# Interface.net
KiCad netlist of a schematic drawn in Altium Designer
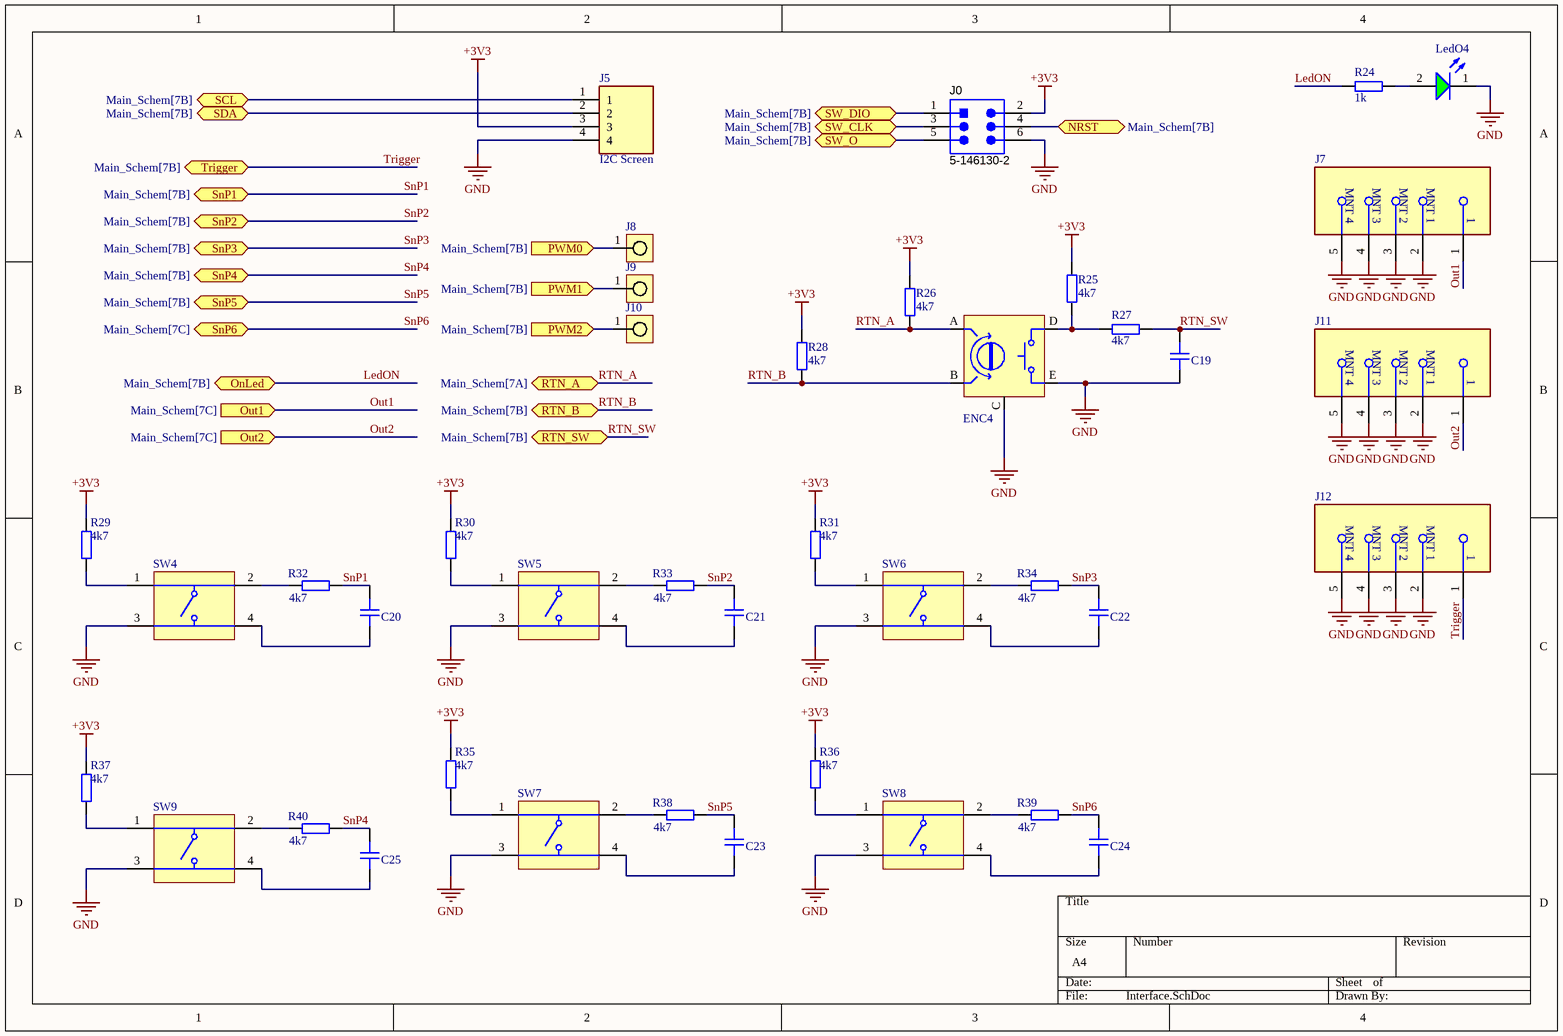
[diagram p0: Interface.SchDoc]

(export (version "E")
  (design (tool "Eeschema 10.0.6"))
  (components
    (comp (ref "C19")
      (value "CAP_0805")
      (footprint "CAP_0805")
      (description "Capacitor SMD 0805")
      (fields (field (name "SOURCE") "Kostas_Psarras_Schem_Lib.SchLib"))
      (libsource (lib "Konstantinos Psarras") (part "CAP_EL_NP_5MM"))
    )
    (comp (ref "C20")
      (value "CAP_0805")
      (footprint "CAP_0805")
      (description "Capacitor SMD 0805")
      (fields (field (name "SOURCE") "Kostas_Psarras_Schem_Lib.SchLib"))
      (libsource (lib "Konstantinos Psarras") (part "CAP_EL_NP_5MM"))
    )
    (comp (ref "C21")
      (value "CAP_0805")
      (footprint "CAP_0805")
      (description "Capacitor SMD 0805")
      (fields (field (name "SOURCE") "Kostas_Psarras_Schem_Lib.SchLib"))
      (libsource (lib "Konstantinos Psarras") (part "CAP_EL_NP_5MM"))
    )
    (comp (ref "C22")
      (value "CAP_0805")
      (footprint "CAP_0805")
      (description "Capacitor SMD 0805")
      (fields (field (name "SOURCE") "Kostas_Psarras_Schem_Lib.SchLib"))
      (libsource (lib "Konstantinos Psarras") (part "CAP_EL_NP_5MM"))
    )
    (comp (ref "C23")
      (value "CAP_0805")
      (footprint "CAP_0805")
      (description "Capacitor SMD 0805")
      (fields (field (name "SOURCE") "Kostas_Psarras_Schem_Lib.SchLib"))
      (libsource (lib "Konstantinos Psarras") (part "CAP_EL_NP_5MM"))
    )
    (comp (ref "C24")
      (value "CAP_0805")
      (footprint "CAP_0805")
      (description "Capacitor SMD 0805")
      (fields (field (name "SOURCE") "Kostas_Psarras_Schem_Lib.SchLib"))
      (libsource (lib "Konstantinos Psarras") (part "CAP_EL_NP_5MM"))
    )
    (comp (ref "C25")
      (value "CAP_0805")
      (footprint "CAP_0805")
      (description "Capacitor SMD 0805")
      (fields (field (name "SOURCE") "Kostas_Psarras_Schem_Lib.SchLib"))
      (libsource (lib "Konstantinos Psarras") (part "CAP_EL_NP_5MM"))
    )
    (comp (ref "ENC4")
      (value "EN11-HSM1BF20")
      (footprint "EN11-HSM")
      (description "Rotary Encoder with Switch 20 Detents 7mm Bushing 20mm Threaded Shaft Vertical")
      (fields (field (name "MANUFACTURER") "TT Electronics"))
      (libsource (lib "Kostas_Psarras_Lib") (part "EN11-HSM1BF20"))
    )
    (comp (ref "J0")
      (value "5-146130-2")
      (footprint "TECO-5-146130-2_V")
      (description "Male Header, Pitch 2.54 mm, 2 x 3 Position, Height 8.13 mm, -65 to 125 degC, RoHS, Tube")
      (fields (field (name "MANUFACTURER") "TE Connectivity"))
      (libsource (lib "Konstantinos Psarras") (part "CN-2P-M-R6"))
    )
    (comp (ref "J5")
      (value "I2C Screen")
      (footprint "RHDR4W70P0X254_1X4_1056X250X850P")
      (description "M20: 4 Pos Receptacle SIL Straight 3mm THT Connector 8.5mm high Tin")
      (fields
        (field (name "MANUFACTURER_PART_NUMBER") "M20-7820446")
        (field (name "MOUSER PART NUMBER") "855-M20-7820446")
        (field (name "SOURCE") "Kostas_Psarras_Schem_Lib.SchLib")
      )
      (libsource (lib "Konstantinos Psarras") (part "M20-7820446"))
    )
    (comp (ref "J7")
      (value "1-1337445-0")
      (footprint "FP-1-1337445-0-MFG")
      (description "CONN BNC JACK STR 50 OHM PCB")
      (libsource (lib "Altium Content Vault") (part "c65b8a639cdaef1819ea20b5466f8fa"))
    )
    (comp (ref "J8")
      (value "SOLDER_PIN_THT")
      (footprint "SOLDER_PIN_THT_1_5")
      (description "Solder Pin 1.5mm Through-Hole")
      (fields (field (name "SOURCE") "Kostas_Psarras_Schem_Lib.SchLib"))
      (libsource (lib "Konstantinos Psarras") (part "SOLDER_PIN_THT"))
    )
    (comp (ref "J9")
      (value "SOLDER_PIN_THT")
      (footprint "SOLDER_PIN_THT_1_5")
      (description "Solder Pin 1.5mm Through-Hole")
      (fields (field (name "SOURCE") "Kostas_Psarras_Schem_Lib.SchLib"))
      (libsource (lib "Konstantinos Psarras") (part "SOLDER_PIN_THT"))
    )
    (comp (ref "J10")
      (value "SOLDER_PIN_THT")
      (footprint "SOLDER_PIN_THT_1_5")
      (description "Solder Pin 1.5mm Through-Hole")
      (fields (field (name "SOURCE") "Kostas_Psarras_Schem_Lib.SchLib"))
      (libsource (lib "Konstantinos Psarras") (part "SOLDER_PIN_THT"))
    )
    (comp (ref "J11")
      (value "1-1337445-0")
      (footprint "FP-1-1337445-0-MFG")
      (description "CONN BNC JACK STR 50 OHM PCB")
      (libsource (lib "Altium Content Vault") (part "c65b8a639cdaef1819ea20b5466f8fa"))
    )
    (comp (ref "J12")
      (value "1-1337445-0")
      (footprint "FP-1-1337445-0-MFG")
      (description "CONN BNC JACK STR 50 OHM PCB")
      (libsource (lib "Altium Content Vault") (part "c65b8a639cdaef1819ea20b5466f8fa"))
    )
    (comp (ref "LedO4")
      (value "151053GS03000")
      (footprint "WL-TMRW_D5.8H11.7")
      (libsource (lib "Altium Content Vault") (part "LED_Green_2A-1K"))
    )
    (comp (ref "R24")
      (value "1k")
      (footprint "RES_0805")
      (description "Resistor SMD 0805")
      (libsource (lib "Schematic-Lib-PhilsLab (1)") (part "RES_0805"))
    )
    (comp (ref "R25")
      (value "4k7")
      (footprint "RES_0805")
      (description "Resistor SMD 0805")
      (fields (field (name "SOURCE") "Kostas_Psarras_Schem_Lib.SchLib"))
      (libsource (lib "Konstantinos Psarras") (part "RES_5931"))
    )
    (comp (ref "R26")
      (value "4k7")
      (footprint "RES_0805")
      (description "Resistor SMD 0805")
      (fields (field (name "SOURCE") "Kostas_Psarras_Schem_Lib.SchLib"))
      (libsource (lib "Konstantinos Psarras") (part "RES_5931"))
    )
    (comp (ref "R27")
      (value "4k7")
      (footprint "RES_0805")
      (description "Resistor SMD 0805")
      (fields (field (name "SOURCE") "Kostas_Psarras_Schem_Lib.SchLib"))
      (libsource (lib "Konstantinos Psarras") (part "RES_5931"))
    )
    (comp (ref "R28")
      (value "4k7")
      (footprint "RES_0805")
      (description "Resistor SMD 0805")
      (fields (field (name "SOURCE") "Kostas_Psarras_Schem_Lib.SchLib"))
      (libsource (lib "Konstantinos Psarras") (part "RES_5931"))
    )
    (comp (ref "R29")
      (value "4k7")
      (footprint "RES_0805")
      (description "Resistor SMD 0805")
      (fields (field (name "SOURCE") "Kostas_Psarras_Schem_Lib.SchLib"))
      (libsource (lib "Konstantinos Psarras") (part "RES_5931"))
    )
    (comp (ref "R30")
      (value "4k7")
      (footprint "RES_0805")
      (description "Resistor SMD 0805")
      (fields (field (name "SOURCE") "Kostas_Psarras_Schem_Lib.SchLib"))
      (libsource (lib "Konstantinos Psarras") (part "RES_5931"))
    )
    (comp (ref "R31")
      (value "4k7")
      (footprint "RES_0805")
      (description "Resistor SMD 0805")
      (fields (field (name "SOURCE") "Kostas_Psarras_Schem_Lib.SchLib"))
      (libsource (lib "Konstantinos Psarras") (part "RES_5931"))
    )
    (comp (ref "R32")
      (value "4k7")
      (footprint "RES_0805")
      (description "Resistor SMD 0805")
      (fields (field (name "SOURCE") "Kostas_Psarras_Schem_Lib.SchLib"))
      (libsource (lib "Konstantinos Psarras") (part "RES_5931"))
    )
    (comp (ref "R33")
      (value "4k7")
      (footprint "RES_0805")
      (description "Resistor SMD 0805")
      (fields (field (name "SOURCE") "Kostas_Psarras_Schem_Lib.SchLib"))
      (libsource (lib "Konstantinos Psarras") (part "RES_5931"))
    )
    (comp (ref "R34")
      (value "4k7")
      (footprint "RES_0805")
      (description "Resistor SMD 0805")
      (fields (field (name "SOURCE") "Kostas_Psarras_Schem_Lib.SchLib"))
      (libsource (lib "Konstantinos Psarras") (part "RES_5931"))
    )
    (comp (ref "R35")
      (value "4k7")
      (footprint "RES_0805")
      (description "Resistor SMD 0805")
      (fields (field (name "SOURCE") "Kostas_Psarras_Schem_Lib.SchLib"))
      (libsource (lib "Konstantinos Psarras") (part "RES_5931"))
    )
    (comp (ref "R36")
      (value "4k7")
      (footprint "RES_0805")
      (description "Resistor SMD 0805")
      (fields (field (name "SOURCE") "Kostas_Psarras_Schem_Lib.SchLib"))
      (libsource (lib "Konstantinos Psarras") (part "RES_5931"))
    )
    (comp (ref "R37")
      (value "4k7")
      (footprint "RES_0805")
      (description "Resistor SMD 0805")
      (fields (field (name "SOURCE") "Kostas_Psarras_Schem_Lib.SchLib"))
      (libsource (lib "Konstantinos Psarras") (part "RES_5931"))
    )
    (comp (ref "R38")
      (value "4k7")
      (footprint "RES_0805")
      (description "Resistor SMD 0805")
      (fields (field (name "SOURCE") "Kostas_Psarras_Schem_Lib.SchLib"))
      (libsource (lib "Konstantinos Psarras") (part "RES_5931"))
    )
    (comp (ref "R39")
      (value "4k7")
      (footprint "RES_0805")
      (description "Resistor SMD 0805")
      (fields (field (name "SOURCE") "Kostas_Psarras_Schem_Lib.SchLib"))
      (libsource (lib "Konstantinos Psarras") (part "RES_5931"))
    )
    (comp (ref "R40")
      (value "4k7")
      (footprint "RES_0805")
      (description "Resistor SMD 0805")
      (fields (field (name "SOURCE") "Kostas_Psarras_Schem_Lib.SchLib"))
      (libsource (lib "Konstantinos Psarras") (part "RES_5931"))
    )
    (comp (ref "SW4")
      (value "1825910-6")
      (footprint "TECO-1825910-6_V")
      (description "Tact Switch, SPST-NO, 0.05 A, -35 to 85 degC, 4-Pin THD, RoHS, Bulk")
      (fields (field (name "MANUFACTURER") "TE Connectivity"))
      (libsource (lib "Altium Content Vault") (part "SW-SPST-4_A"))
    )
    (comp (ref "SW5")
      (value "1825910-6")
      (footprint "TECO-1825910-6_V")
      (description "Tact Switch, SPST-NO, 0.05 A, -35 to 85 degC, 4-Pin THD, RoHS, Bulk")
      (fields (field (name "MANUFACTURER") "TE Connectivity"))
      (libsource (lib "Altium Content Vault") (part "SW-SPST-4_A"))
    )
    (comp (ref "SW6")
      (value "1825910-6")
      (footprint "TECO-1825910-6_V")
      (description "Tact Switch, SPST-NO, 0.05 A, -35 to 85 degC, 4-Pin THD, RoHS, Bulk")
      (fields (field (name "MANUFACTURER") "TE Connectivity"))
      (libsource (lib "Altium Content Vault") (part "SW-SPST-4_A"))
    )
    (comp (ref "SW7")
      (value "1825910-6")
      (footprint "TECO-1825910-6_V")
      (description "Tact Switch, SPST-NO, 0.05 A, -35 to 85 degC, 4-Pin THD, RoHS, Bulk")
      (fields (field (name "MANUFACTURER") "TE Connectivity"))
      (libsource (lib "Altium Content Vault") (part "SW-SPST-4_A"))
    )
    (comp (ref "SW8")
      (value "1825910-6")
      (footprint "TECO-1825910-6_V")
      (description "Tact Switch, SPST-NO, 0.05 A, -35 to 85 degC, 4-Pin THD, RoHS, Bulk")
      (fields (field (name "MANUFACTURER") "TE Connectivity"))
      (libsource (lib "Altium Content Vault") (part "SW-SPST-4_A"))
    )
    (comp (ref "SW9")
      (value "1825910-6")
      (footprint "TECO-1825910-6_V")
      (description "Tact Switch, SPST-NO, 0.05 A, -35 to 85 degC, 4-Pin THD, RoHS, Bulk")
      (fields (field (name "MANUFACTURER") "TE Connectivity"))
      (libsource (lib "Altium Content Vault") (part "SW-SPST-4_A"))
    )
  )
  (nets
    (net (code "1") (name "+3V3") (class "Default")
      (node (ref "J0") (pin "2") (pinfunction "2_2") (pintype "passive"))
      (node (ref "J5") (pin "3") (pinfunction "3_3") (pintype "passive"))
      (node (ref "R25") (pin "2") (pinfunction "2_2") (pintype "passive"))
      (node (ref "R26") (pin "2") (pinfunction "2_2") (pintype "passive"))
      (node (ref "R28") (pin "2") (pinfunction "2_2") (pintype "passive"))
      (node (ref "R29") (pin "2") (pinfunction "2_2") (pintype "passive"))
      (node (ref "R30") (pin "2") (pinfunction "2_2") (pintype "passive"))
      (node (ref "R31") (pin "2") (pinfunction "2_2") (pintype "passive"))
      (node (ref "R35") (pin "2") (pinfunction "2_2") (pintype "passive"))
      (node (ref "R36") (pin "2") (pinfunction "2_2") (pintype "passive"))
      (node (ref "R37") (pin "2") (pinfunction "2_2") (pintype "passive"))
    )
    (net (code "2") (name "/LedON") (class "Default")
      (node (ref "R24") (pin "2") (pinfunction "2_2") (pintype "passive"))
    )
    (net (code "3") (name "/NRST") (class "Default")
      (node (ref "J0") (pin "4") (pinfunction "4_4") (pintype "passive"))
    )
    (net (code "4") (name "/Out1") (class "Default")
      (node (ref "J7") (pin "1") (pinfunction "1_1") (pintype "passive"))
    )
    (net (code "5") (name "/Out2") (class "Default")
      (node (ref "J11") (pin "1") (pinfunction "1_1") (pintype "passive"))
    )
    (net (code "6") (name "/PWM0") (class "Default")
      (node (ref "J8") (pin "1") (pinfunction "1_1") (pintype "passive"))
    )
    (net (code "7") (name "/PWM1") (class "Default")
      (node (ref "J9") (pin "1") (pinfunction "1_1") (pintype "passive"))
    )
    (net (code "8") (name "/PWM2") (class "Default")
      (node (ref "J10") (pin "1") (pinfunction "1_1") (pintype "passive"))
    )
    (net (code "9") (name "/RTN_A") (class "Default")
      (node (ref "ENC4") (pin "A") (pinfunction "A_A") (pintype "passive"))
      (node (ref "R26") (pin "1") (pinfunction "1_1") (pintype "passive"))
    )
    (net (code "10") (name "/RTN_B") (class "Default")
      (node (ref "ENC4") (pin "B") (pinfunction "B_B") (pintype "passive"))
      (node (ref "R28") (pin "1") (pinfunction "1_1") (pintype "passive"))
    )
    (net (code "11") (name "/RTN_SW") (class "Default")
      (node (ref "C19") (pin "2") (pinfunction "2_2") (pintype "passive"))
      (node (ref "R27") (pin "1") (pinfunction "1_1") (pintype "passive"))
    )
    (net (code "12") (name "/SCL") (class "Default")
      (node (ref "J5") (pin "1") (pinfunction "1_1") (pintype "passive"))
    )
    (net (code "13") (name "/SDA") (class "Default")
      (node (ref "J5") (pin "2") (pinfunction "2_2") (pintype "passive"))
    )
    (net (code "14") (name "/SW_CLK") (class "Default")
      (node (ref "J0") (pin "3") (pinfunction "3_3") (pintype "passive"))
    )
    (net (code "15") (name "/SW_DIO") (class "Default")
      (node (ref "J0") (pin "1") (pinfunction "1_1") (pintype "passive"))
    )
    (net (code "16") (name "/SW_O") (class "Default")
      (node (ref "J0") (pin "5") (pinfunction "5_5") (pintype "passive"))
    )
    (net (code "17") (name "/SnP1") (class "Default")
      (node (ref "C20") (pin "2") (pinfunction "2_2") (pintype "passive"))
      (node (ref "R32") (pin "1") (pinfunction "1_1") (pintype "passive"))
    )
    (net (code "18") (name "/SnP2") (class "Default")
      (node (ref "C21") (pin "2") (pinfunction "2_2") (pintype "passive"))
      (node (ref "R33") (pin "1") (pinfunction "1_1") (pintype "passive"))
    )
    (net (code "19") (name "/SnP3") (class "Default")
      (node (ref "C22") (pin "2") (pinfunction "2_2") (pintype "passive"))
      (node (ref "R34") (pin "1") (pinfunction "1_1") (pintype "passive"))
    )
    (net (code "20") (name "/SnP4") (class "Default")
      (node (ref "C25") (pin "2") (pinfunction "2_2") (pintype "passive"))
      (node (ref "R40") (pin "1") (pinfunction "1_1") (pintype "passive"))
    )
    (net (code "21") (name "/SnP5") (class "Default")
      (node (ref "C23") (pin "2") (pinfunction "2_2") (pintype "passive"))
      (node (ref "R38") (pin "1") (pinfunction "1_1") (pintype "passive"))
    )
    (net (code "22") (name "/SnP6") (class "Default")
      (node (ref "C24") (pin "2") (pinfunction "2_2") (pintype "passive"))
      (node (ref "R39") (pin "1") (pinfunction "1_1") (pintype "passive"))
    )
    (net (code "23") (name "/Trigger") (class "Default")
      (node (ref "J12") (pin "1") (pinfunction "1_1") (pintype "passive"))
    )
    (net (code "24") (name "GND") (class "Default")
      (node (ref "C19") (pin "1") (pinfunction "1_1") (pintype "passive"))
      (node (ref "ENC4") (pin "C") (pinfunction "GND_C") (pintype "power_in"))
      (node (ref "ENC4") (pin "E") (pinfunction "E_E") (pintype "passive"))
      (node (ref "J0") (pin "6") (pinfunction "6_6") (pintype "passive"))
      (node (ref "J11") (pin "2") (pinfunction "MNT_1_2") (pintype "passive"))
      (node (ref "J11") (pin "3") (pinfunction "MNT_2_3") (pintype "passive"))
      (node (ref "J11") (pin "4") (pinfunction "MNT_3_4") (pintype "passive"))
      (node (ref "J11") (pin "5") (pinfunction "MNT_4_5") (pintype "passive"))
      (node (ref "J12") (pin "2") (pinfunction "MNT_1_2") (pintype "passive"))
      (node (ref "J12") (pin "3") (pinfunction "MNT_2_3") (pintype "passive"))
      (node (ref "J12") (pin "4") (pinfunction "MNT_3_4") (pintype "passive"))
      (node (ref "J12") (pin "5") (pinfunction "MNT_4_5") (pintype "passive"))
      (node (ref "J5") (pin "4") (pinfunction "4_4") (pintype "passive"))
      (node (ref "J7") (pin "2") (pinfunction "MNT_1_2") (pintype "passive"))
      (node (ref "J7") (pin "3") (pinfunction "MNT_2_3") (pintype "passive"))
      (node (ref "J7") (pin "4") (pinfunction "MNT_3_4") (pintype "passive"))
      (node (ref "J7") (pin "5") (pinfunction "MNT_4_5") (pintype "passive"))
      (node (ref "LedO4") (pin "1") (pinfunction "K_1") (pintype "passive"))
      (node (ref "SW4") (pin "3") (pinfunction "3_3") (pintype "passive"))
      (node (ref "SW5") (pin "3") (pinfunction "3_3") (pintype "passive"))
      (node (ref "SW6") (pin "3") (pinfunction "3_3") (pintype "passive"))
      (node (ref "SW7") (pin "3") (pinfunction "3_3") (pintype "passive"))
      (node (ref "SW8") (pin "3") (pinfunction "3_3") (pintype "passive"))
      (node (ref "SW9") (pin "3") (pinfunction "3_3") (pintype "passive"))
    )
    (net (code "25") (name "Net-(C20-Pad1)") (class "Default")
      (node (ref "C20") (pin "1") (pinfunction "1_1") (pintype "passive"))
      (node (ref "SW4") (pin "4") (pinfunction "4_4") (pintype "passive"))
    )
    (net (code "26") (name "Net-(C21-Pad1)") (class "Default")
      (node (ref "C21") (pin "1") (pinfunction "1_1") (pintype "passive"))
      (node (ref "SW5") (pin "4") (pinfunction "4_4") (pintype "passive"))
    )
    (net (code "27") (name "Net-(C22-Pad1)") (class "Default")
      (node (ref "C22") (pin "1") (pinfunction "1_1") (pintype "passive"))
      (node (ref "SW6") (pin "4") (pinfunction "4_4") (pintype "passive"))
    )
    (net (code "28") (name "Net-(C23-Pad1)") (class "Default")
      (node (ref "C23") (pin "1") (pinfunction "1_1") (pintype "passive"))
      (node (ref "SW7") (pin "4") (pinfunction "4_4") (pintype "passive"))
    )
    (net (code "29") (name "Net-(C24-Pad1)") (class "Default")
      (node (ref "C24") (pin "1") (pinfunction "1_1") (pintype "passive"))
      (node (ref "SW8") (pin "4") (pinfunction "4_4") (pintype "passive"))
    )
    (net (code "30") (name "Net-(C25-Pad1)") (class "Default")
      (node (ref "C25") (pin "1") (pinfunction "1_1") (pintype "passive"))
      (node (ref "SW9") (pin "4") (pinfunction "4_4") (pintype "passive"))
    )
    (net (code "31") (name "Net-(ENC4-PadD)") (class "Default")
      (node (ref "ENC4") (pin "D") (pinfunction "D_D") (pintype "passive"))
      (node (ref "R25") (pin "1") (pinfunction "1_1") (pintype "passive"))
      (node (ref "R27") (pin "2") (pinfunction "2_2") (pintype "passive"))
    )
    (net (code "32") (name "Net-(LedO4-A)") (class "Default")
      (node (ref "LedO4") (pin "2") (pinfunction "A_2") (pintype "passive"))
      (node (ref "R24") (pin "1") (pinfunction "1_1") (pintype "passive"))
    )
    (net (code "33") (name "Net-(R29-Pad1)") (class "Default")
      (node (ref "R29") (pin "1") (pinfunction "1_1") (pintype "passive"))
      (node (ref "SW4") (pin "1") (pinfunction "1_1") (pintype "passive"))
    )
    (net (code "34") (name "Net-(R30-Pad1)") (class "Default")
      (node (ref "R30") (pin "1") (pinfunction "1_1") (pintype "passive"))
      (node (ref "SW5") (pin "1") (pinfunction "1_1") (pintype "passive"))
    )
    (net (code "35") (name "Net-(R31-Pad1)") (class "Default")
      (node (ref "R31") (pin "1") (pinfunction "1_1") (pintype "passive"))
      (node (ref "SW6") (pin "1") (pinfunction "1_1") (pintype "passive"))
    )
    (net (code "36") (name "Net-(R32-Pad2)") (class "Default")
      (node (ref "R32") (pin "2") (pinfunction "2_2") (pintype "passive"))
      (node (ref "SW4") (pin "2") (pinfunction "2_2") (pintype "passive"))
    )
    (net (code "37") (name "Net-(R33-Pad2)") (class "Default")
      (node (ref "R33") (pin "2") (pinfunction "2_2") (pintype "passive"))
      (node (ref "SW5") (pin "2") (pinfunction "2_2") (pintype "passive"))
    )
    (net (code "38") (name "Net-(R34-Pad2)") (class "Default")
      (node (ref "R34") (pin "2") (pinfunction "2_2") (pintype "passive"))
      (node (ref "SW6") (pin "2") (pinfunction "2_2") (pintype "passive"))
    )
    (net (code "39") (name "Net-(R35-Pad1)") (class "Default")
      (node (ref "R35") (pin "1") (pinfunction "1_1") (pintype "passive"))
      (node (ref "SW7") (pin "1") (pinfunction "1_1") (pintype "passive"))
    )
    (net (code "40") (name "Net-(R36-Pad1)") (class "Default")
      (node (ref "R36") (pin "1") (pinfunction "1_1") (pintype "passive"))
      (node (ref "SW8") (pin "1") (pinfunction "1_1") (pintype "passive"))
    )
    (net (code "41") (name "Net-(R37-Pad1)") (class "Default")
      (node (ref "R37") (pin "1") (pinfunction "1_1") (pintype "passive"))
      (node (ref "SW9") (pin "1") (pinfunction "1_1") (pintype "passive"))
    )
    (net (code "42") (name "Net-(R38-Pad2)") (class "Default")
      (node (ref "R38") (pin "2") (pinfunction "2_2") (pintype "passive"))
      (node (ref "SW7") (pin "2") (pinfunction "2_2") (pintype "passive"))
    )
    (net (code "43") (name "Net-(R39-Pad2)") (class "Default")
      (node (ref "R39") (pin "2") (pinfunction "2_2") (pintype "passive"))
      (node (ref "SW8") (pin "2") (pinfunction "2_2") (pintype "passive"))
    )
    (net (code "44") (name "Net-(R40-Pad2)") (class "Default")
      (node (ref "R40") (pin "2") (pinfunction "2_2") (pintype "passive"))
      (node (ref "SW9") (pin "2") (pinfunction "2_2") (pintype "passive"))
    )
  )
)
